# Motor.net
KiCad netlist of a schematic drawn in Altium Designer
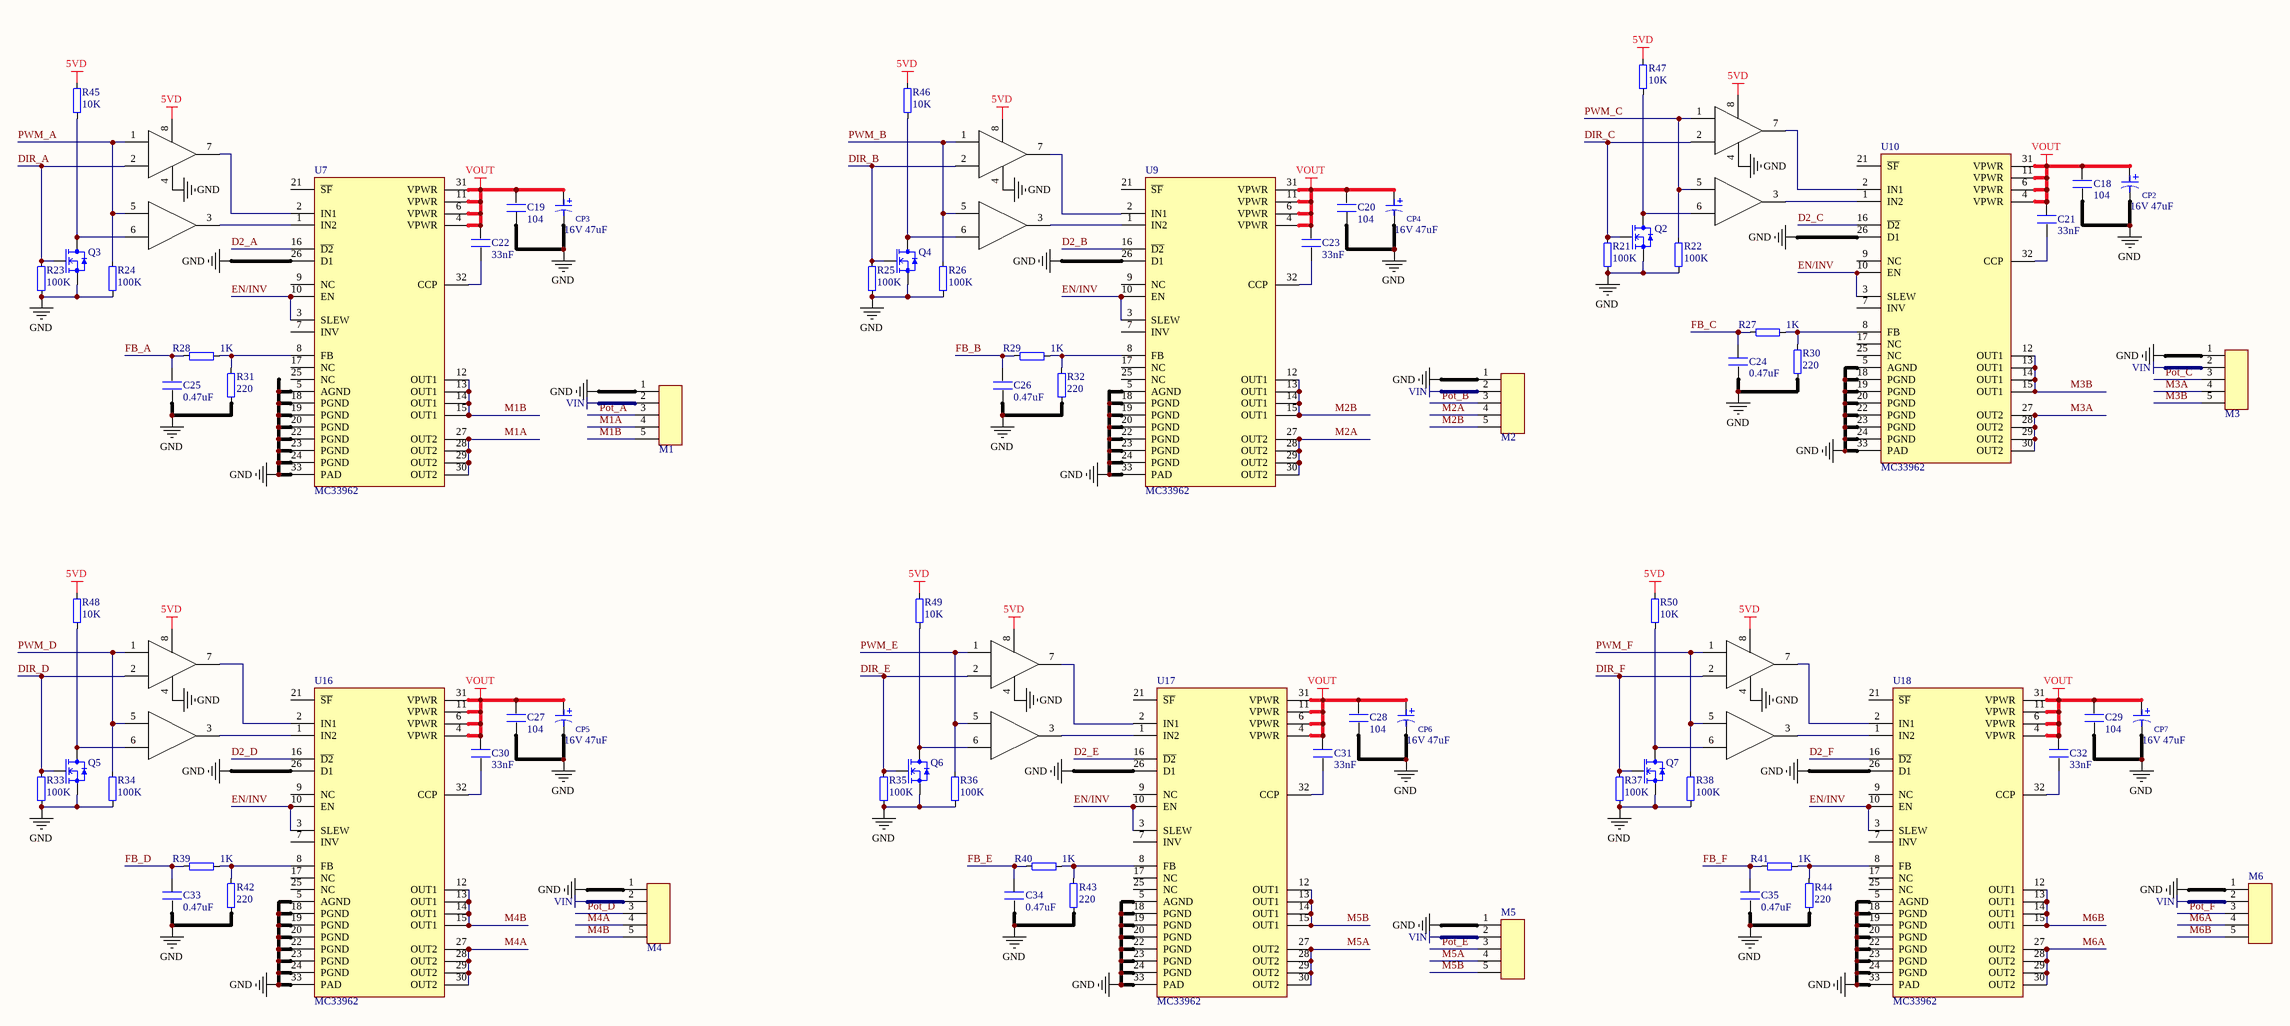
[diagram p0: Motor.SchDoc]

(export (version "E")
  (design (tool "Eeschema 10.0.6"))
  (components
    (comp (ref "C18") (value "104") (footprint "SM0603C") (libsource (lib "BAO") (part "C")))
    (comp (ref "C19") (value "104") (footprint "SM0603C") (libsource (lib "BAO") (part "C")))
    (comp (ref "C20") (value "104") (footprint "SM0603C") (libsource (lib "BAO") (part "C")))
    (comp (ref "C21") (value "33nF") (footprint "SM0603C") (libsource (lib "BAO") (part "C")))
    (comp (ref "C22") (value "33nF") (footprint "SM0603C") (libsource (lib "BAO") (part "C")))
    (comp (ref "C23") (value "33nF") (footprint "SM0603C") (libsource (lib "BAO") (part "C")))
    (comp (ref "C24") (value "0.47uF") (footprint "SM0603C") (libsource (lib "BAO") (part "C")))
    (comp (ref "C25") (value "0.47uF") (footprint "SM0603C") (libsource (lib "BAO") (part "C")))
    (comp (ref "C26") (value "0.47uF") (footprint "SM0603C") (libsource (lib "BAO") (part "C")))
    (comp (ref "C27") (value "104") (footprint "SM0603C") (libsource (lib "BAO") (part "C")))
    (comp (ref "C28") (value "104") (footprint "SM0603C") (libsource (lib "BAO") (part "C")))
    (comp (ref "C29") (value "104") (footprint "SM0603C") (libsource (lib "BAO") (part "C")))
    (comp (ref "C30") (value "33nF") (footprint "SM0603C") (libsource (lib "BAO") (part "C")))
    (comp (ref "C31") (value "33nF") (footprint "SM0603C") (libsource (lib "BAO") (part "C")))
    (comp (ref "C32") (value "33nF") (footprint "SM0603C") (libsource (lib "BAO") (part "C")))
    (comp (ref "C33") (value "0.47uF") (footprint "SM0603C") (libsource (lib "BAO") (part "C")))
    (comp (ref "C34") (value "0.47uF") (footprint "SM0603C") (libsource (lib "BAO") (part "C")))
    (comp (ref "C35") (value "0.47uF") (footprint "SM0603C") (libsource (lib "BAO") (part "C")))
    (comp (ref "CP2")
      (value "16V 47uF")
      (footprint "SMD5-Al")
      (description "Cap, 22uF, 20%, 16V")
      (libsource (lib "DigiMagusLib_CIS") (part "Cap Pol"))
    )
    (comp (ref "CP3")
      (value "16V 47uF")
      (footprint "SMD5-Al")
      (description "Cap, 22uF, 20%, 16V")
      (libsource (lib "DigiMagusLib_CIS") (part "Cap Pol"))
    )
    (comp (ref "CP4")
      (value "16V 47uF")
      (footprint "SMD5-Al")
      (description "Cap, 22uF, 20%, 16V")
      (libsource (lib "DigiMagusLib_CIS") (part "Cap Pol"))
    )
    (comp (ref "CP5")
      (value "16V 47uF")
      (footprint "SMD5-Al")
      (description "Cap, 22uF, 20%, 16V")
      (libsource (lib "DigiMagusLib_CIS") (part "Cap Pol"))
    )
    (comp (ref "CP6")
      (value "16V 47uF")
      (footprint "SMD5-Al")
      (description "Cap, 22uF, 20%, 16V")
      (libsource (lib "DigiMagusLib_CIS") (part "Cap Pol"))
    )
    (comp (ref "CP7")
      (value "16V 47uF")
      (footprint "SMD5-Al")
      (description "Cap, 22uF, 20%, 16V")
      (libsource (lib "DigiMagusLib_CIS") (part "Cap Pol"))
    )
    (comp (ref "M1") (value "JC5") (footprint "FCI_SFW5R-1STE1LF") (libsource (lib "Schlib1") (part "JC5")))
    (comp (ref "M2") (value "JC5") (footprint "FCI_SFW5R-1STE1LF") (libsource (lib "Schlib1") (part "JC5")))
    (comp (ref "M3") (value "JC5") (footprint "FCI_SFW5R-1STE1LF") (libsource (lib "Schlib1") (part "JC5")))
    (comp (ref "M4") (value "JC5") (footprint "FCI_SFW5R-1STE1LF") (libsource (lib "Schlib1") (part "JC5")))
    (comp (ref "M5") (value "JC5") (footprint "FCI_SFW5R-1STE1LF") (libsource (lib "Schlib1") (part "JC5")))
    (comp (ref "M6") (value "JC5") (footprint "FCI_SFW5R-1STE1LF") (libsource (lib "Schlib1") (part "JC5")))
    (comp (ref "Q2")
      (value "2N7002")
      (footprint "SOT23-3")
      (description "Mos/N, 2N7002, 7.5 OHM, 0.5A, SOT23-3, Supertex")
      (fields (field (name "PART NUMBER") "2.1.4.40.0270020"))
      (libsource (lib "DigiMagusLib_CIS") (part "MofFet-N"))
    )
    (comp (ref "Q3")
      (value "2N7002")
      (footprint "SOT23-3")
      (description "Mos/N, 2N7002, 7.5 OHM, 0.5A, SOT23-3, Supertex")
      (fields (field (name "PART NUMBER") "2.1.4.40.0270020"))
      (libsource (lib "DigiMagusLib_CIS") (part "MofFet-N"))
    )
    (comp (ref "Q4")
      (value "2N7002")
      (footprint "SOT23-3")
      (description "Mos/N, 2N7002, 7.5 OHM, 0.5A, SOT23-3, Supertex")
      (fields (field (name "PART NUMBER") "2.1.4.40.0270020"))
      (libsource (lib "DigiMagusLib_CIS") (part "MofFet-N"))
    )
    (comp (ref "Q5")
      (value "2N7002")
      (footprint "SOT23-3")
      (description "Mos/N, 2N7002, 7.5 OHM, 0.5A, SOT23-3, Supertex")
      (fields (field (name "PART NUMBER") "2.1.4.40.0270020"))
      (libsource (lib "DigiMagusLib_CIS") (part "MofFet-N"))
    )
    (comp (ref "Q6")
      (value "2N7002")
      (footprint "SOT23-3")
      (description "Mos/N, 2N7002, 7.5 OHM, 0.5A, SOT23-3, Supertex")
      (fields (field (name "PART NUMBER") "2.1.4.40.0270020"))
      (libsource (lib "DigiMagusLib_CIS") (part "MofFet-N"))
    )
    (comp (ref "Q7")
      (value "2N7002")
      (footprint "SOT23-3")
      (description "Mos/N, 2N7002, 7.5 OHM, 0.5A, SOT23-3, Supertex")
      (fields (field (name "PART NUMBER") "2.1.4.40.0270020"))
      (libsource (lib "DigiMagusLib_CIS") (part "MofFet-N"))
    )
    (comp (ref "R21") (value "100K") (footprint "SM0603R") (libsource (lib "电阻") (part "RES")))
    (comp (ref "R22") (value "100K") (footprint "SM0603R") (libsource (lib "电阻") (part "RES")))
    (comp (ref "R23") (value "100K") (footprint "SM0603R") (libsource (lib "电阻") (part "RES")))
    (comp (ref "R24") (value "100K") (footprint "SM0603R") (libsource (lib "电阻") (part "RES")))
    (comp (ref "R25") (value "100K") (footprint "SM0603R") (libsource (lib "电阻") (part "RES")))
    (comp (ref "R26") (value "100K") (footprint "SM0603R") (libsource (lib "电阻") (part "RES")))
    (comp (ref "R27") (value "1K") (footprint "SM0603R") (libsource (lib "电阻") (part "RES")))
    (comp (ref "R28") (value "1K") (footprint "SM0603R") (libsource (lib "电阻") (part "RES")))
    (comp (ref "R29") (value "1K") (footprint "SM0603R") (libsource (lib "电阻") (part "RES")))
    (comp (ref "R30") (value "220") (footprint "SM0603R") (libsource (lib "电阻") (part "RES")))
    (comp (ref "R31") (value "220") (footprint "SM0603R") (libsource (lib "电阻") (part "RES")))
    (comp (ref "R32") (value "220") (footprint "SM0603R") (libsource (lib "电阻") (part "RES")))
    (comp (ref "R33") (value "100K") (footprint "SM0603R") (libsource (lib "电阻") (part "RES")))
    (comp (ref "R34") (value "100K") (footprint "SM0603R") (libsource (lib "电阻") (part "RES")))
    (comp (ref "R35") (value "100K") (footprint "SM0603R") (libsource (lib "电阻") (part "RES")))
    (comp (ref "R36") (value "100K") (footprint "SM0603R") (libsource (lib "电阻") (part "RES")))
    (comp (ref "R37") (value "100K") (footprint "SM0603R") (libsource (lib "电阻") (part "RES")))
    (comp (ref "R38") (value "100K") (footprint "SM0603R") (libsource (lib "电阻") (part "RES")))
    (comp (ref "R39") (value "1K") (footprint "SM0603R") (libsource (lib "电阻") (part "RES")))
    (comp (ref "R40") (value "1K") (footprint "SM0603R") (libsource (lib "电阻") (part "RES")))
    (comp (ref "R41") (value "1K") (footprint "SM0603R") (libsource (lib "电阻") (part "RES")))
    (comp (ref "R42") (value "220") (footprint "SM0603R") (libsource (lib "电阻") (part "RES")))
    (comp (ref "R43") (value "220") (footprint "SM0603R") (libsource (lib "电阻") (part "RES")))
    (comp (ref "R44") (value "220") (footprint "SM0603R") (libsource (lib "电阻") (part "RES")))
    (comp (ref "R45") (value "10K") (footprint "SM0603R") (libsource (lib "电阻") (part "RES")))
    (comp (ref "R46") (value "10K") (footprint "SM0603R") (libsource (lib "电阻") (part "RES")))
    (comp (ref "R47") (value "10K") (footprint "SM0603R") (libsource (lib "电阻") (part "RES")))
    (comp (ref "R48") (value "10K") (footprint "SM0603R") (libsource (lib "电阻") (part "RES")))
    (comp (ref "R49") (value "10K") (footprint "SM0603R") (libsource (lib "电阻") (part "RES")))
    (comp (ref "R50") (value "10K") (footprint "SM0603R") (libsource (lib "电阻") (part "RES")))
    (comp (ref "U4")
      (value "74XXX")
      (footprint "LC-VSSOP-8_2x2.3x05P")
      (libsource (lib "Project") (part "74XXX"))
    )
    (comp (ref "U5")
      (value "74XXX")
      (footprint "LC-VSSOP-8_2x2.3x05P")
      (libsource (lib "Project") (part "74XXX"))
    )
    (comp (ref "U6")
      (value "74XXX")
      (footprint "LC-VSSOP-8_2x2.3x05P")
      (libsource (lib "Project") (part "74XXX"))
    )
    (comp (ref "U7")
      (value "MC33962")
      (footprint "PQFN32_0P8_8X8_SLUG")
      (libsource (lib "Schlib1") (part "MC33962"))
    )
    (comp (ref "U8")
      (value "74XXX")
      (footprint "LC-VSSOP-8_2x2.3x05P")
      (libsource (lib "Project") (part "74XXX"))
    )
    (comp (ref "U9")
      (value "MC33962")
      (footprint "PQFN32_0P8_8X8_SLUG")
      (libsource (lib "Schlib1") (part "MC33962"))
    )
    (comp (ref "U10")
      (value "MC33962")
      (footprint "PQFN32_0P8_8X8_SLUG")
      (libsource (lib "Schlib1") (part "MC33962"))
    )
    (comp (ref "U11")
      (value "74XXX")
      (footprint "LC-VSSOP-8_2x2.3x05P")
      (libsource (lib "Project") (part "74XXX"))
    )
    (comp (ref "U12")
      (value "74XXX")
      (footprint "LC-VSSOP-8_2x2.3x05P")
      (libsource (lib "Project") (part "74XXX"))
    )
    (comp (ref "U16")
      (value "MC33962")
      (footprint "PQFN32_0P8_8X8_SLUG")
      (libsource (lib "Schlib1") (part "MC33962"))
    )
    (comp (ref "U17")
      (value "MC33962")
      (footprint "PQFN32_0P8_8X8_SLUG")
      (libsource (lib "Schlib1") (part "MC33962"))
    )
    (comp (ref "U18")
      (value "MC33962")
      (footprint "PQFN32_0P8_8X8_SLUG")
      (libsource (lib "Schlib1") (part "MC33962"))
    )
  )
  (nets
    (net (code "1") (name "/D2_A") (class "Default")
      (node (ref "U7") (pin "16") (pinfunction "~{D2}_16") (pintype "passive"))
    )
    (net (code "2") (name "/D2_B") (class "Default")
      (node (ref "U9") (pin "16") (pinfunction "~{D2}_16") (pintype "passive"))
    )
    (net (code "3") (name "/D2_C") (class "Default")
      (node (ref "U10") (pin "16") (pinfunction "~{D2}_16") (pintype "passive"))
    )
    (net (code "4") (name "/D2_D") (class "Default")
      (node (ref "U16") (pin "16") (pinfunction "~{D2}_16") (pintype "passive"))
    )
    (net (code "5") (name "/D2_E") (class "Default")
      (node (ref "U17") (pin "16") (pinfunction "~{D2}_16") (pintype "passive"))
    )
    (net (code "6") (name "/D2_F") (class "Default")
      (node (ref "U18") (pin "16") (pinfunction "~{D2}_16") (pintype "passive"))
    )
    (net (code "7") (name "/DIR_A") (class "Default")
      (node (ref "Q3") (pin "1") (pinfunction "G_1") (pintype "passive"))
      (node (ref "R23") (pin "2") (pinfunction "2_2") (pintype "passive"))
      (node (ref "U4") (pin "2") (pinfunction "2_2") (pintype "passive"))
    )
    (net (code "8") (name "/DIR_B") (class "Default")
      (node (ref "Q4") (pin "1") (pinfunction "G_1") (pintype "passive"))
      (node (ref "R25") (pin "2") (pinfunction "2_2") (pintype "passive"))
      (node (ref "U5") (pin "2") (pinfunction "2_2") (pintype "passive"))
    )
    (net (code "9") (name "/DIR_C") (class "Default")
      (node (ref "Q2") (pin "1") (pinfunction "G_1") (pintype "passive"))
      (node (ref "R21") (pin "2") (pinfunction "2_2") (pintype "passive"))
      (node (ref "U6") (pin "2") (pinfunction "2_2") (pintype "passive"))
    )
    (net (code "10") (name "/DIR_D") (class "Default")
      (node (ref "Q5") (pin "1") (pinfunction "G_1") (pintype "passive"))
      (node (ref "R33") (pin "2") (pinfunction "2_2") (pintype "passive"))
      (node (ref "U8") (pin "2") (pinfunction "2_2") (pintype "passive"))
    )
    (net (code "11") (name "/DIR_E") (class "Default")
      (node (ref "Q6") (pin "1") (pinfunction "G_1") (pintype "passive"))
      (node (ref "R35") (pin "2") (pinfunction "2_2") (pintype "passive"))
      (node (ref "U11") (pin "2") (pinfunction "2_2") (pintype "passive"))
    )
    (net (code "12") (name "/DIR_F") (class "Default")
      (node (ref "Q7") (pin "1") (pinfunction "G_1") (pintype "passive"))
      (node (ref "R37") (pin "2") (pinfunction "2_2") (pintype "passive"))
      (node (ref "U12") (pin "2") (pinfunction "2_2") (pintype "passive"))
    )
    (net (code "13") (name "/EN{slash}INV") (class "Default")
      (node (ref "U10") (pin "10") (pinfunction "EN_10") (pintype "passive"))
      (node (ref "U10") (pin "3") (pinfunction "SLEW_3") (pintype "passive"))
      (node (ref "U16") (pin "10") (pinfunction "EN_10") (pintype "passive"))
      (node (ref "U16") (pin "3") (pinfunction "SLEW_3") (pintype "passive"))
      (node (ref "U17") (pin "10") (pinfunction "EN_10") (pintype "passive"))
      (node (ref "U17") (pin "3") (pinfunction "SLEW_3") (pintype "passive"))
      (node (ref "U18") (pin "10") (pinfunction "EN_10") (pintype "passive"))
      (node (ref "U18") (pin "3") (pinfunction "SLEW_3") (pintype "passive"))
      (node (ref "U7") (pin "10") (pinfunction "EN_10") (pintype "passive"))
      (node (ref "U7") (pin "3") (pinfunction "SLEW_3") (pintype "passive"))
      (node (ref "U9") (pin "10") (pinfunction "EN_10") (pintype "passive"))
      (node (ref "U9") (pin "3") (pinfunction "SLEW_3") (pintype "passive"))
    )
    (net (code "14") (name "/FB_A") (class "Default")
      (node (ref "C25") (pin "1") (pintype "passive"))
      (node (ref "R28") (pin "1") (pinfunction "1_1") (pintype "passive"))
    )
    (net (code "15") (name "/FB_B") (class "Default")
      (node (ref "C26") (pin "1") (pintype "passive"))
      (node (ref "R29") (pin "1") (pinfunction "1_1") (pintype "passive"))
    )
    (net (code "16") (name "/FB_C") (class "Default")
      (node (ref "C24") (pin "1") (pintype "passive"))
      (node (ref "R27") (pin "1") (pinfunction "1_1") (pintype "passive"))
    )
    (net (code "17") (name "/FB_D") (class "Default")
      (node (ref "C33") (pin "1") (pintype "passive"))
      (node (ref "R39") (pin "1") (pinfunction "1_1") (pintype "passive"))
    )
    (net (code "18") (name "/FB_E") (class "Default")
      (node (ref "C34") (pin "1") (pintype "passive"))
      (node (ref "R40") (pin "1") (pinfunction "1_1") (pintype "passive"))
    )
    (net (code "19") (name "/FB_F") (class "Default")
      (node (ref "C35") (pin "1") (pintype "passive"))
      (node (ref "R41") (pin "1") (pinfunction "1_1") (pintype "passive"))
    )
    (net (code "20") (name "/M1A") (class "Default")
      (node (ref "M1") (pin "4") (pinfunction "4_4") (pintype "passive"))
      (node (ref "U7") (pin "27") (pinfunction "OUT2_27") (pintype "passive"))
      (node (ref "U7") (pin "28") (pinfunction "OUT2_28") (pintype "passive"))
      (node (ref "U7") (pin "29") (pinfunction "OUT2_29") (pintype "passive"))
      (node (ref "U7") (pin "30") (pinfunction "OUT2_30") (pintype "passive"))
    )
    (net (code "21") (name "/M1B") (class "Default")
      (node (ref "M1") (pin "5") (pinfunction "5_5") (pintype "passive"))
      (node (ref "U7") (pin "12") (pinfunction "OUT1_12") (pintype "passive"))
      (node (ref "U7") (pin "13") (pinfunction "OUT1_13") (pintype "passive"))
      (node (ref "U7") (pin "14") (pinfunction "OUT1_14") (pintype "passive"))
      (node (ref "U7") (pin "15") (pinfunction "OUT1_15") (pintype "passive"))
    )
    (net (code "22") (name "/M2A") (class "Default")
      (node (ref "M2") (pin "4") (pinfunction "4_4") (pintype "passive"))
      (node (ref "U9") (pin "27") (pinfunction "OUT2_27") (pintype "passive"))
      (node (ref "U9") (pin "28") (pinfunction "OUT2_28") (pintype "passive"))
      (node (ref "U9") (pin "29") (pinfunction "OUT2_29") (pintype "passive"))
      (node (ref "U9") (pin "30") (pinfunction "OUT2_30") (pintype "passive"))
    )
    (net (code "23") (name "/M2B") (class "Default")
      (node (ref "M2") (pin "5") (pinfunction "5_5") (pintype "passive"))
      (node (ref "U9") (pin "12") (pinfunction "OUT1_12") (pintype "passive"))
      (node (ref "U9") (pin "13") (pinfunction "OUT1_13") (pintype "passive"))
      (node (ref "U9") (pin "14") (pinfunction "OUT1_14") (pintype "passive"))
      (node (ref "U9") (pin "15") (pinfunction "OUT1_15") (pintype "passive"))
    )
    (net (code "24") (name "/M3A") (class "Default")
      (node (ref "M3") (pin "4") (pinfunction "4_4") (pintype "passive"))
      (node (ref "U10") (pin "27") (pinfunction "OUT2_27") (pintype "passive"))
      (node (ref "U10") (pin "28") (pinfunction "OUT2_28") (pintype "passive"))
      (node (ref "U10") (pin "29") (pinfunction "OUT2_29") (pintype "passive"))
      (node (ref "U10") (pin "30") (pinfunction "OUT2_30") (pintype "passive"))
    )
    (net (code "25") (name "/M3B") (class "Default")
      (node (ref "M3") (pin "5") (pinfunction "5_5") (pintype "passive"))
      (node (ref "U10") (pin "12") (pinfunction "OUT1_12") (pintype "passive"))
      (node (ref "U10") (pin "13") (pinfunction "OUT1_13") (pintype "passive"))
      (node (ref "U10") (pin "14") (pinfunction "OUT1_14") (pintype "passive"))
      (node (ref "U10") (pin "15") (pinfunction "OUT1_15") (pintype "passive"))
    )
    (net (code "26") (name "/M4A") (class "Default")
      (node (ref "M4") (pin "4") (pinfunction "4_4") (pintype "passive"))
      (node (ref "U16") (pin "27") (pinfunction "OUT2_27") (pintype "passive"))
      (node (ref "U16") (pin "28") (pinfunction "OUT2_28") (pintype "passive"))
      (node (ref "U16") (pin "29") (pinfunction "OUT2_29") (pintype "passive"))
      (node (ref "U16") (pin "30") (pinfunction "OUT2_30") (pintype "passive"))
    )
    (net (code "27") (name "/M4B") (class "Default")
      (node (ref "M4") (pin "5") (pinfunction "5_5") (pintype "passive"))
      (node (ref "U16") (pin "12") (pinfunction "OUT1_12") (pintype "passive"))
      (node (ref "U16") (pin "13") (pinfunction "OUT1_13") (pintype "passive"))
      (node (ref "U16") (pin "14") (pinfunction "OUT1_14") (pintype "passive"))
      (node (ref "U16") (pin "15") (pinfunction "OUT1_15") (pintype "passive"))
    )
    (net (code "28") (name "/M5A") (class "Default")
      (node (ref "M5") (pin "4") (pinfunction "4_4") (pintype "passive"))
      (node (ref "U17") (pin "27") (pinfunction "OUT2_27") (pintype "passive"))
      (node (ref "U17") (pin "28") (pinfunction "OUT2_28") (pintype "passive"))
      (node (ref "U17") (pin "29") (pinfunction "OUT2_29") (pintype "passive"))
      (node (ref "U17") (pin "30") (pinfunction "OUT2_30") (pintype "passive"))
    )
    (net (code "29") (name "/M5B") (class "Default")
      (node (ref "M5") (pin "5") (pinfunction "5_5") (pintype "passive"))
      (node (ref "U17") (pin "12") (pinfunction "OUT1_12") (pintype "passive"))
      (node (ref "U17") (pin "13") (pinfunction "OUT1_13") (pintype "passive"))
      (node (ref "U17") (pin "14") (pinfunction "OUT1_14") (pintype "passive"))
      (node (ref "U17") (pin "15") (pinfunction "OUT1_15") (pintype "passive"))
    )
    (net (code "30") (name "/M6A") (class "Default")
      (node (ref "M6") (pin "4") (pinfunction "4_4") (pintype "passive"))
      (node (ref "U18") (pin "27") (pinfunction "OUT2_27") (pintype "passive"))
      (node (ref "U18") (pin "28") (pinfunction "OUT2_28") (pintype "passive"))
      (node (ref "U18") (pin "29") (pinfunction "OUT2_29") (pintype "passive"))
      (node (ref "U18") (pin "30") (pinfunction "OUT2_30") (pintype "passive"))
    )
    (net (code "31") (name "/M6B") (class "Default")
      (node (ref "M6") (pin "5") (pinfunction "5_5") (pintype "passive"))
      (node (ref "U18") (pin "12") (pinfunction "OUT1_12") (pintype "passive"))
      (node (ref "U18") (pin "13") (pinfunction "OUT1_13") (pintype "passive"))
      (node (ref "U18") (pin "14") (pinfunction "OUT1_14") (pintype "passive"))
      (node (ref "U18") (pin "15") (pinfunction "OUT1_15") (pintype "passive"))
    )
    (net (code "32") (name "/PWM_A") (class "Default")
      (node (ref "R24") (pin "2") (pinfunction "2_2") (pintype "passive"))
      (node (ref "U4") (pin "1") (pinfunction "1_1") (pintype "passive"))
      (node (ref "U4") (pin "5") (pinfunction "5_5") (pintype "passive"))
    )
    (net (code "33") (name "/PWM_B") (class "Default")
      (node (ref "R26") (pin "2") (pinfunction "2_2") (pintype "passive"))
      (node (ref "U5") (pin "1") (pinfunction "1_1") (pintype "passive"))
      (node (ref "U5") (pin "5") (pinfunction "5_5") (pintype "passive"))
    )
    (net (code "34") (name "/PWM_C") (class "Default")
      (node (ref "R22") (pin "2") (pinfunction "2_2") (pintype "passive"))
      (node (ref "U6") (pin "1") (pinfunction "1_1") (pintype "passive"))
      (node (ref "U6") (pin "5") (pinfunction "5_5") (pintype "passive"))
    )
    (net (code "35") (name "/PWM_D") (class "Default")
      (node (ref "R34") (pin "2") (pinfunction "2_2") (pintype "passive"))
      (node (ref "U8") (pin "1") (pinfunction "1_1") (pintype "passive"))
      (node (ref "U8") (pin "5") (pinfunction "5_5") (pintype "passive"))
    )
    (net (code "36") (name "/PWM_E") (class "Default")
      (node (ref "R36") (pin "2") (pinfunction "2_2") (pintype "passive"))
      (node (ref "U11") (pin "1") (pinfunction "1_1") (pintype "passive"))
      (node (ref "U11") (pin "5") (pinfunction "5_5") (pintype "passive"))
    )
    (net (code "37") (name "/PWM_F") (class "Default")
      (node (ref "R38") (pin "2") (pinfunction "2_2") (pintype "passive"))
      (node (ref "U12") (pin "1") (pinfunction "1_1") (pintype "passive"))
      (node (ref "U12") (pin "5") (pinfunction "5_5") (pintype "passive"))
    )
    (net (code "38") (name "/Pot_A") (class "Default")
      (node (ref "M1") (pin "3") (pinfunction "3_3") (pintype "passive"))
    )
    (net (code "39") (name "/Pot_B") (class "Default")
      (node (ref "M2") (pin "3") (pinfunction "3_3") (pintype "passive"))
    )
    (net (code "40") (name "/Pot_C") (class "Default")
      (node (ref "M3") (pin "3") (pinfunction "3_3") (pintype "passive"))
    )
    (net (code "41") (name "/Pot_D") (class "Default")
      (node (ref "M4") (pin "3") (pinfunction "3_3") (pintype "passive"))
    )
    (net (code "42") (name "/Pot_E") (class "Default")
      (node (ref "M5") (pin "3") (pinfunction "3_3") (pintype "passive"))
    )
    (net (code "43") (name "/Pot_F") (class "Default")
      (node (ref "M6") (pin "3") (pinfunction "3_3") (pintype "passive"))
    )
    (net (code "44") (name "5VD") (class "Default")
      (node (ref "R45") (pin "2") (pinfunction "2_2") (pintype "passive"))
      (node (ref "R46") (pin "2") (pinfunction "2_2") (pintype "passive"))
      (node (ref "R47") (pin "2") (pinfunction "2_2") (pintype "passive"))
      (node (ref "R48") (pin "2") (pinfunction "2_2") (pintype "passive"))
      (node (ref "R49") (pin "2") (pinfunction "2_2") (pintype "passive"))
      (node (ref "R50") (pin "2") (pinfunction "2_2") (pintype "passive"))
      (node (ref "U11") (pin "8") (pinfunction "8_8") (pintype "passive"))
      (node (ref "U12") (pin "8") (pinfunction "8_8") (pintype "passive"))
      (node (ref "U4") (pin "8") (pinfunction "8_8") (pintype "passive"))
      (node (ref "U5") (pin "8") (pinfunction "8_8") (pintype "passive"))
      (node (ref "U6") (pin "8") (pinfunction "8_8") (pintype "passive"))
      (node (ref "U8") (pin "8") (pinfunction "8_8") (pintype "passive"))
    )
    (net (code "45") (name "GND") (class "Default")
      (node (ref "C18") (pin "1") (pintype "passive"))
      (node (ref "C19") (pin "1") (pintype "passive"))
      (node (ref "C20") (pin "1") (pintype "passive"))
      (node (ref "C24") (pin "2") (pintype "passive"))
      (node (ref "C25") (pin "2") (pintype "passive"))
      (node (ref "C26") (pin "2") (pintype "passive"))
      (node (ref "C27") (pin "1") (pintype "passive"))
      (node (ref "C28") (pin "1") (pintype "passive"))
      (node (ref "C29") (pin "1") (pintype "passive"))
      (node (ref "C33") (pin "2") (pintype "passive"))
      (node (ref "C34") (pin "2") (pintype "passive"))
      (node (ref "C35") (pin "2") (pintype "passive"))
      (node (ref "CP2") (pin "2") (pintype "passive"))
      (node (ref "CP3") (pin "2") (pintype "passive"))
      (node (ref "CP4") (pin "2") (pintype "passive"))
      (node (ref "CP5") (pin "2") (pintype "passive"))
      (node (ref "CP6") (pin "2") (pintype "passive"))
      (node (ref "CP7") (pin "2") (pintype "passive"))
      (node (ref "M1") (pin "1") (pinfunction "1_1") (pintype "passive"))
      (node (ref "M2") (pin "1") (pinfunction "1_1") (pintype "passive"))
      (node (ref "M3") (pin "1") (pinfunction "1_1") (pintype "passive"))
      (node (ref "M4") (pin "1") (pinfunction "1_1") (pintype "passive"))
      (node (ref "M5") (pin "1") (pinfunction "1_1") (pintype "passive"))
      (node (ref "M6") (pin "1") (pinfunction "1_1") (pintype "passive"))
      (node (ref "Q2") (pin "2") (pinfunction "S_2") (pintype "passive"))
      (node (ref "Q3") (pin "2") (pinfunction "S_2") (pintype "passive"))
      (node (ref "Q4") (pin "2") (pinfunction "S_2") (pintype "passive"))
      (node (ref "Q5") (pin "2") (pinfunction "S_2") (pintype "passive"))
      (node (ref "Q6") (pin "2") (pinfunction "S_2") (pintype "passive"))
      (node (ref "Q7") (pin "2") (pinfunction "S_2") (pintype "passive"))
      (node (ref "R21") (pin "1") (pinfunction "1_1") (pintype "passive"))
      (node (ref "R22") (pin "1") (pinfunction "1_1") (pintype "passive"))
      (node (ref "R23") (pin "1") (pinfunction "1_1") (pintype "passive"))
      (node (ref "R24") (pin "1") (pinfunction "1_1") (pintype "passive"))
      (node (ref "R25") (pin "1") (pinfunction "1_1") (pintype "passive"))
      (node (ref "R26") (pin "1") (pinfunction "1_1") (pintype "passive"))
      (node (ref "R30") (pin "1") (pinfunction "1_1") (pintype "passive"))
      (node (ref "R31") (pin "1") (pinfunction "1_1") (pintype "passive"))
      (node (ref "R32") (pin "1") (pinfunction "1_1") (pintype "passive"))
      (node (ref "R33") (pin "1") (pinfunction "1_1") (pintype "passive"))
      (node (ref "R34") (pin "1") (pinfunction "1_1") (pintype "passive"))
      (node (ref "R35") (pin "1") (pinfunction "1_1") (pintype "passive"))
      (node (ref "R36") (pin "1") (pinfunction "1_1") (pintype "passive"))
      (node (ref "R37") (pin "1") (pinfunction "1_1") (pintype "passive"))
      (node (ref "R38") (pin "1") (pinfunction "1_1") (pintype "passive"))
      (node (ref "R42") (pin "1") (pinfunction "1_1") (pintype "passive"))
      (node (ref "R43") (pin "1") (pinfunction "1_1") (pintype "passive"))
      (node (ref "R44") (pin "1") (pinfunction "1_1") (pintype "passive"))
      (node (ref "U10") (pin "18") (pinfunction "PGND_18") (pintype "passive"))
      (node (ref "U10") (pin "19") (pinfunction "PGND_19") (pintype "passive"))
      (node (ref "U10") (pin "20") (pinfunction "PGND_20") (pintype "passive"))
      (node (ref "U10") (pin "22") (pinfunction "PGND_22") (pintype "passive"))
      (node (ref "U10") (pin "23") (pinfunction "PGND_23") (pintype "passive"))
      (node (ref "U10") (pin "24") (pinfunction "PGND_24") (pintype "passive"))
      (node (ref "U10") (pin "26") (pinfunction "D1_26") (pintype "passive"))
      (node (ref "U10") (pin "33") (pinfunction "PAD_33") (pintype "passive"))
      (node (ref "U10") (pin "5") (pinfunction "AGND_5") (pintype "passive"))
      (node (ref "U11") (pin "4") (pinfunction "4_4") (pintype "passive"))
      (node (ref "U12") (pin "4") (pinfunction "4_4") (pintype "passive"))
      (node (ref "U16") (pin "18") (pinfunction "PGND_18") (pintype "passive"))
      (node (ref "U16") (pin "19") (pinfunction "PGND_19") (pintype "passive"))
      (node (ref "U16") (pin "20") (pinfunction "PGND_20") (pintype "passive"))
      (node (ref "U16") (pin "22") (pinfunction "PGND_22") (pintype "passive"))
      (node (ref "U16") (pin "23") (pinfunction "PGND_23") (pintype "passive"))
      (node (ref "U16") (pin "24") (pinfunction "PGND_24") (pintype "passive"))
      (node (ref "U16") (pin "26") (pinfunction "D1_26") (pintype "passive"))
      (node (ref "U16") (pin "33") (pinfunction "PAD_33") (pintype "passive"))
      (node (ref "U16") (pin "5") (pinfunction "AGND_5") (pintype "passive"))
      (node (ref "U17") (pin "18") (pinfunction "PGND_18") (pintype "passive"))
      (node (ref "U17") (pin "19") (pinfunction "PGND_19") (pintype "passive"))
      (node (ref "U17") (pin "20") (pinfunction "PGND_20") (pintype "passive"))
      (node (ref "U17") (pin "22") (pinfunction "PGND_22") (pintype "passive"))
      (node (ref "U17") (pin "23") (pinfunction "PGND_23") (pintype "passive"))
      (node (ref "U17") (pin "24") (pinfunction "PGND_24") (pintype "passive"))
      (node (ref "U17") (pin "26") (pinfunction "D1_26") (pintype "passive"))
      (node (ref "U17") (pin "33") (pinfunction "PAD_33") (pintype "passive"))
      (node (ref "U17") (pin "5") (pinfunction "AGND_5") (pintype "passive"))
      (node (ref "U18") (pin "18") (pinfunction "PGND_18") (pintype "passive"))
      (node (ref "U18") (pin "19") (pinfunction "PGND_19") (pintype "passive"))
      (node (ref "U18") (pin "20") (pinfunction "PGND_20") (pintype "passive"))
      (node (ref "U18") (pin "22") (pinfunction "PGND_22") (pintype "passive"))
      (node (ref "U18") (pin "23") (pinfunction "PGND_23") (pintype "passive"))
      (node (ref "U18") (pin "24") (pinfunction "PGND_24") (pintype "passive"))
      (node (ref "U18") (pin "26") (pinfunction "D1_26") (pintype "passive"))
      (node (ref "U18") (pin "33") (pinfunction "PAD_33") (pintype "passive"))
      (node (ref "U18") (pin "5") (pinfunction "AGND_5") (pintype "passive"))
      (node (ref "U4") (pin "4") (pinfunction "4_4") (pintype "passive"))
      (node (ref "U5") (pin "4") (pinfunction "4_4") (pintype "passive"))
      (node (ref "U6") (pin "4") (pinfunction "4_4") (pintype "passive"))
      (node (ref "U7") (pin "18") (pinfunction "PGND_18") (pintype "passive"))
      (node (ref "U7") (pin "19") (pinfunction "PGND_19") (pintype "passive"))
      (node (ref "U7") (pin "20") (pinfunction "PGND_20") (pintype "passive"))
      (node (ref "U7") (pin "22") (pinfunction "PGND_22") (pintype "passive"))
      (node (ref "U7") (pin "23") (pinfunction "PGND_23") (pintype "passive"))
      (node (ref "U7") (pin "24") (pinfunction "PGND_24") (pintype "passive"))
      (node (ref "U7") (pin "26") (pinfunction "D1_26") (pintype "passive"))
      (node (ref "U7") (pin "33") (pinfunction "PAD_33") (pintype "passive"))
      (node (ref "U7") (pin "5") (pinfunction "AGND_5") (pintype "passive"))
      (node (ref "U8") (pin "4") (pinfunction "4_4") (pintype "passive"))
      (node (ref "U9") (pin "18") (pinfunction "PGND_18") (pintype "passive"))
      (node (ref "U9") (pin "19") (pinfunction "PGND_19") (pintype "passive"))
      (node (ref "U9") (pin "20") (pinfunction "PGND_20") (pintype "passive"))
      (node (ref "U9") (pin "22") (pinfunction "PGND_22") (pintype "passive"))
      (node (ref "U9") (pin "23") (pinfunction "PGND_23") (pintype "passive"))
      (node (ref "U9") (pin "24") (pinfunction "PGND_24") (pintype "passive"))
      (node (ref "U9") (pin "26") (pinfunction "D1_26") (pintype "passive"))
      (node (ref "U9") (pin "33") (pinfunction "PAD_33") (pintype "passive"))
      (node (ref "U9") (pin "5") (pinfunction "AGND_5") (pintype "passive"))
    )
    (net (code "46") (name "Net-(Q2-D)") (class "Default")
      (node (ref "Q2") (pin "3") (pinfunction "D_3") (pintype "passive"))
      (node (ref "R47") (pin "1") (pinfunction "1_1") (pintype "passive"))
      (node (ref "U6") (pin "6") (pinfunction "6_6") (pintype "passive"))
    )
    (net (code "47") (name "Net-(Q3-D)") (class "Default")
      (node (ref "Q3") (pin "3") (pinfunction "D_3") (pintype "passive"))
      (node (ref "R45") (pin "1") (pinfunction "1_1") (pintype "passive"))
      (node (ref "U4") (pin "6") (pinfunction "6_6") (pintype "passive"))
    )
    (net (code "48") (name "Net-(Q4-D)") (class "Default")
      (node (ref "Q4") (pin "3") (pinfunction "D_3") (pintype "passive"))
      (node (ref "R46") (pin "1") (pinfunction "1_1") (pintype "passive"))
      (node (ref "U5") (pin "6") (pinfunction "6_6") (pintype "passive"))
    )
    (net (code "49") (name "Net-(Q5-D)") (class "Default")
      (node (ref "Q5") (pin "3") (pinfunction "D_3") (pintype "passive"))
      (node (ref "R48") (pin "1") (pinfunction "1_1") (pintype "passive"))
      (node (ref "U8") (pin "6") (pinfunction "6_6") (pintype "passive"))
    )
    (net (code "50") (name "Net-(Q6-D)") (class "Default")
      (node (ref "Q6") (pin "3") (pinfunction "D_3") (pintype "passive"))
      (node (ref "R49") (pin "1") (pinfunction "1_1") (pintype "passive"))
      (node (ref "U11") (pin "6") (pinfunction "6_6") (pintype "passive"))
    )
    (net (code "51") (name "Net-(Q7-D)") (class "Default")
      (node (ref "Q7") (pin "3") (pinfunction "D_3") (pintype "passive"))
      (node (ref "R50") (pin "1") (pinfunction "1_1") (pintype "passive"))
      (node (ref "U12") (pin "6") (pinfunction "6_6") (pintype "passive"))
    )
    (net (code "52") (name "Net-(U7-CCP)") (class "Default")
      (node (ref "C22") (pin "2") (pintype "passive"))
      (node (ref "U7") (pin "32") (pinfunction "CCP_32") (pintype "passive"))
    )
    (net (code "53") (name "Net-(U7-FB)") (class "Default")
      (node (ref "R28") (pin "2") (pinfunction "2_2") (pintype "passive"))
      (node (ref "R31") (pin "2") (pinfunction "2_2") (pintype "passive"))
      (node (ref "U7") (pin "8") (pinfunction "FB_8") (pintype "passive"))
    )
    (net (code "54") (name "Net-(U7-IN1)") (class "Default")
      (node (ref "U4") (pin "7") (pinfunction "7_7") (pintype "passive"))
      (node (ref "U7") (pin "2") (pinfunction "IN1_2") (pintype "passive"))
    )
    (net (code "55") (name "Net-(U7-IN2)") (class "Default")
      (node (ref "U4") (pin "3") (pinfunction "3_3") (pintype "passive"))
      (node (ref "U7") (pin "1") (pinfunction "IN2_1") (pintype "passive"))
    )
    (net (code "56") (name "Net-(U9-CCP)") (class "Default")
      (node (ref "C23") (pin "2") (pintype "passive"))
      (node (ref "U9") (pin "32") (pinfunction "CCP_32") (pintype "passive"))
    )
    (net (code "57") (name "Net-(U9-FB)") (class "Default")
      (node (ref "R29") (pin "2") (pinfunction "2_2") (pintype "passive"))
      (node (ref "R32") (pin "2") (pinfunction "2_2") (pintype "passive"))
      (node (ref "U9") (pin "8") (pinfunction "FB_8") (pintype "passive"))
    )
    (net (code "58") (name "Net-(U9-IN1)") (class "Default")
      (node (ref "U5") (pin "7") (pinfunction "7_7") (pintype "passive"))
      (node (ref "U9") (pin "2") (pinfunction "IN1_2") (pintype "passive"))
    )
    (net (code "59") (name "Net-(U9-IN2)") (class "Default")
      (node (ref "U5") (pin "3") (pinfunction "3_3") (pintype "passive"))
      (node (ref "U9") (pin "1") (pinfunction "IN2_1") (pintype "passive"))
    )
    (net (code "60") (name "Net-(U10-CCP)") (class "Default")
      (node (ref "C21") (pin "2") (pintype "passive"))
      (node (ref "U10") (pin "32") (pinfunction "CCP_32") (pintype "passive"))
    )
    (net (code "61") (name "Net-(U10-FB)") (class "Default")
      (node (ref "R27") (pin "2") (pinfunction "2_2") (pintype "passive"))
      (node (ref "R30") (pin "2") (pinfunction "2_2") (pintype "passive"))
      (node (ref "U10") (pin "8") (pinfunction "FB_8") (pintype "passive"))
    )
    (net (code "62") (name "Net-(U10-IN1)") (class "Default")
      (node (ref "U10") (pin "2") (pinfunction "IN1_2") (pintype "passive"))
      (node (ref "U6") (pin "7") (pinfunction "7_7") (pintype "passive"))
    )
    (net (code "63") (name "Net-(U10-IN2)") (class "Default")
      (node (ref "U10") (pin "1") (pinfunction "IN2_1") (pintype "passive"))
      (node (ref "U6") (pin "3") (pinfunction "3_3") (pintype "passive"))
    )
    (net (code "64") (name "Net-(U16-CCP)") (class "Default")
      (node (ref "C30") (pin "2") (pintype "passive"))
      (node (ref "U16") (pin "32") (pinfunction "CCP_32") (pintype "passive"))
    )
    (net (code "65") (name "Net-(U16-FB)") (class "Default")
      (node (ref "R39") (pin "2") (pinfunction "2_2") (pintype "passive"))
      (node (ref "R42") (pin "2") (pinfunction "2_2") (pintype "passive"))
      (node (ref "U16") (pin "8") (pinfunction "FB_8") (pintype "passive"))
    )
    (net (code "66") (name "Net-(U16-IN1)") (class "Default")
      (node (ref "U16") (pin "2") (pinfunction "IN1_2") (pintype "passive"))
      (node (ref "U8") (pin "7") (pinfunction "7_7") (pintype "passive"))
    )
    (net (code "67") (name "Net-(U16-IN2)") (class "Default")
      (node (ref "U16") (pin "1") (pinfunction "IN2_1") (pintype "passive"))
      (node (ref "U8") (pin "3") (pinfunction "3_3") (pintype "passive"))
    )
    (net (code "68") (name "Net-(U17-CCP)") (class "Default")
      (node (ref "C31") (pin "2") (pintype "passive"))
      (node (ref "U17") (pin "32") (pinfunction "CCP_32") (pintype "passive"))
    )
    (net (code "69") (name "Net-(U17-FB)") (class "Default")
      (node (ref "R40") (pin "2") (pinfunction "2_2") (pintype "passive"))
      (node (ref "R43") (pin "2") (pinfunction "2_2") (pintype "passive"))
      (node (ref "U17") (pin "8") (pinfunction "FB_8") (pintype "passive"))
    )
    (net (code "70") (name "Net-(U17-IN1)") (class "Default")
      (node (ref "U11") (pin "7") (pinfunction "7_7") (pintype "passive"))
      (node (ref "U17") (pin "2") (pinfunction "IN1_2") (pintype "passive"))
    )
    (net (code "71") (name "Net-(U17-IN2)") (class "Default")
      (node (ref "U11") (pin "3") (pinfunction "3_3") (pintype "passive"))
      (node (ref "U17") (pin "1") (pinfunction "IN2_1") (pintype "passive"))
    )
    (net (code "72") (name "Net-(U18-CCP)") (class "Default")
      (node (ref "C32") (pin "2") (pintype "passive"))
      (node (ref "U18") (pin "32") (pinfunction "CCP_32") (pintype "passive"))
    )
    (net (code "73") (name "Net-(U18-FB)") (class "Default")
      (node (ref "R41") (pin "2") (pinfunction "2_2") (pintype "passive"))
      (node (ref "R44") (pin "2") (pinfunction "2_2") (pintype "passive"))
      (node (ref "U18") (pin "8") (pinfunction "FB_8") (pintype "passive"))
    )
    (net (code "74") (name "Net-(U18-IN1)") (class "Default")
      (node (ref "U12") (pin "7") (pinfunction "7_7") (pintype "passive"))
      (node (ref "U18") (pin "2") (pinfunction "IN1_2") (pintype "passive"))
    )
    (net (code "75") (name "Net-(U18-IN2)") (class "Default")
      (node (ref "U12") (pin "3") (pinfunction "3_3") (pintype "passive"))
      (node (ref "U18") (pin "1") (pinfunction "IN2_1") (pintype "passive"))
    )
    (net (code "76") (name "VIN") (class "Default")
      (node (ref "M1") (pin "2") (pinfunction "2_2") (pintype "passive"))
      (node (ref "M2") (pin "2") (pinfunction "2_2") (pintype "passive"))
      (node (ref "M3") (pin "2") (pinfunction "2_2") (pintype "passive"))
      (node (ref "M4") (pin "2") (pinfunction "2_2") (pintype "passive"))
      (node (ref "M5") (pin "2") (pinfunction "2_2") (pintype "passive"))
      (node (ref "M6") (pin "2") (pinfunction "2_2") (pintype "passive"))
    )
    (net (code "77") (name "VOUT") (class "Default")
      (node (ref "C18") (pin "2") (pintype "passive"))
      (node (ref "C19") (pin "2") (pintype "passive"))
      (node (ref "C20") (pin "2") (pintype "passive"))
      (node (ref "C21") (pin "1") (pintype "passive"))
      (node (ref "C22") (pin "1") (pintype "passive"))
      (node (ref "C23") (pin "1") (pintype "passive"))
      (node (ref "C27") (pin "2") (pintype "passive"))
      (node (ref "C28") (pin "2") (pintype "passive"))
      (node (ref "C29") (pin "2") (pintype "passive"))
      (node (ref "C30") (pin "1") (pintype "passive"))
      (node (ref "C31") (pin "1") (pintype "passive"))
      (node (ref "C32") (pin "1") (pintype "passive"))
      (node (ref "CP2") (pin "1") (pintype "passive"))
      (node (ref "CP3") (pin "1") (pintype "passive"))
      (node (ref "CP4") (pin "1") (pintype "passive"))
      (node (ref "CP5") (pin "1") (pintype "passive"))
      (node (ref "CP6") (pin "1") (pintype "passive"))
      (node (ref "CP7") (pin "1") (pintype "passive"))
      (node (ref "U10") (pin "11") (pinfunction "VPWR_11") (pintype "passive"))
      (node (ref "U10") (pin "31") (pinfunction "VPWR_31") (pintype "passive"))
      (node (ref "U10") (pin "4") (pinfunction "VPWR_4") (pintype "passive"))
      (node (ref "U10") (pin "6") (pinfunction "VPWR_6") (pintype "passive"))
      (node (ref "U16") (pin "11") (pinfunction "VPWR_11") (pintype "passive"))
      (node (ref "U16") (pin "31") (pinfunction "VPWR_31") (pintype "passive"))
      (node (ref "U16") (pin "4") (pinfunction "VPWR_4") (pintype "passive"))
      (node (ref "U16") (pin "6") (pinfunction "VPWR_6") (pintype "passive"))
      (node (ref "U17") (pin "11") (pinfunction "VPWR_11") (pintype "passive"))
      (node (ref "U17") (pin "31") (pinfunction "VPWR_31") (pintype "passive"))
      (node (ref "U17") (pin "4") (pinfunction "VPWR_4") (pintype "passive"))
      (node (ref "U17") (pin "6") (pinfunction "VPWR_6") (pintype "passive"))
      (node (ref "U18") (pin "11") (pinfunction "VPWR_11") (pintype "passive"))
      (node (ref "U18") (pin "31") (pinfunction "VPWR_31") (pintype "passive"))
      (node (ref "U18") (pin "4") (pinfunction "VPWR_4") (pintype "passive"))
      (node (ref "U18") (pin "6") (pinfunction "VPWR_6") (pintype "passive"))
      (node (ref "U7") (pin "11") (pinfunction "VPWR_11") (pintype "passive"))
      (node (ref "U7") (pin "31") (pinfunction "VPWR_31") (pintype "passive"))
      (node (ref "U7") (pin "4") (pinfunction "VPWR_4") (pintype "passive"))
      (node (ref "U7") (pin "6") (pinfunction "VPWR_6") (pintype "passive"))
      (node (ref "U9") (pin "11") (pinfunction "VPWR_11") (pintype "passive"))
      (node (ref "U9") (pin "31") (pinfunction "VPWR_31") (pintype "passive"))
      (node (ref "U9") (pin "4") (pinfunction "VPWR_4") (pintype "passive"))
      (node (ref "U9") (pin "6") (pinfunction "VPWR_6") (pintype "passive"))
    )
    (net (code "78") (name "unconnected-(U7-INV-Pad7)") (class "Default")
      (node (ref "U7") (pin "7") (pinfunction "INV_7") (pintype "passive"))
    )
    (net (code "79") (name "unconnected-(U7-NC-Pad9)") (class "Default")
      (node (ref "U7") (pin "9") (pinfunction "NC_9") (pintype "passive"))
    )
    (net (code "80") (name "unconnected-(U7-NC-Pad17)") (class "Default")
      (node (ref "U7") (pin "17") (pinfunction "NC_17") (pintype "passive"))
    )
    (net (code "81") (name "unconnected-(U7-NC-Pad25)") (class "Default")
      (node (ref "U7") (pin "25") (pinfunction "NC_25") (pintype "passive"))
    )
    (net (code "82") (name "unconnected-(U7-~{SF}-Pad21)") (class "Default")
      (node (ref "U7") (pin "21") (pinfunction "~{SF}_21") (pintype "passive"))
    )
    (net (code "83") (name "unconnected-(U9-INV-Pad7)") (class "Default")
      (node (ref "U9") (pin "7") (pinfunction "INV_7") (pintype "passive"))
    )
    (net (code "84") (name "unconnected-(U9-NC-Pad9)") (class "Default")
      (node (ref "U9") (pin "9") (pinfunction "NC_9") (pintype "passive"))
    )
    (net (code "85") (name "unconnected-(U9-NC-Pad17)") (class "Default")
      (node (ref "U9") (pin "17") (pinfunction "NC_17") (pintype "passive"))
    )
    (net (code "86") (name "unconnected-(U9-NC-Pad25)") (class "Default")
      (node (ref "U9") (pin "25") (pinfunction "NC_25") (pintype "passive"))
    )
    (net (code "87") (name "unconnected-(U9-~{SF}-Pad21)") (class "Default")
      (node (ref "U9") (pin "21") (pinfunction "~{SF}_21") (pintype "passive"))
    )
    (net (code "88") (name "unconnected-(U10-INV-Pad7)") (class "Default")
      (node (ref "U10") (pin "7") (pinfunction "INV_7") (pintype "passive"))
    )
    (net (code "89") (name "unconnected-(U10-NC-Pad9)") (class "Default")
      (node (ref "U10") (pin "9") (pinfunction "NC_9") (pintype "passive"))
    )
    (net (code "90") (name "unconnected-(U10-NC-Pad17)") (class "Default")
      (node (ref "U10") (pin "17") (pinfunction "NC_17") (pintype "passive"))
    )
    (net (code "91") (name "unconnected-(U10-NC-Pad25)") (class "Default")
      (node (ref "U10") (pin "25") (pinfunction "NC_25") (pintype "passive"))
    )
    (net (code "92") (name "unconnected-(U10-~{SF}-Pad21)") (class "Default")
      (node (ref "U10") (pin "21") (pinfunction "~{SF}_21") (pintype "passive"))
    )
    (net (code "93") (name "unconnected-(U16-INV-Pad7)") (class "Default")
      (node (ref "U16") (pin "7") (pinfunction "INV_7") (pintype "passive"))
    )
    (net (code "94") (name "unconnected-(U16-NC-Pad9)") (class "Default")
      (node (ref "U16") (pin "9") (pinfunction "NC_9") (pintype "passive"))
    )
    (net (code "95") (name "unconnected-(U16-NC-Pad17)") (class "Default")
      (node (ref "U16") (pin "17") (pinfunction "NC_17") (pintype "passive"))
    )
    (net (code "96") (name "unconnected-(U16-NC-Pad25)") (class "Default")
      (node (ref "U16") (pin "25") (pinfunction "NC_25") (pintype "passive"))
    )
    (net (code "97") (name "unconnected-(U16-~{SF}-Pad21)") (class "Default")
      (node (ref "U16") (pin "21") (pinfunction "~{SF}_21") (pintype "passive"))
    )
    (net (code "98") (name "unconnected-(U17-INV-Pad7)") (class "Default")
      (node (ref "U17") (pin "7") (pinfunction "INV_7") (pintype "passive"))
    )
    (net (code "99") (name "unconnected-(U17-NC-Pad9)") (class "Default")
      (node (ref "U17") (pin "9") (pinfunction "NC_9") (pintype "passive"))
    )
    (net (code "100") (name "unconnected-(U17-NC-Pad17)") (class "Default")
      (node (ref "U17") (pin "17") (pinfunction "NC_17") (pintype "passive"))
    )
    (net (code "101") (name "unconnected-(U17-NC-Pad25)") (class "Default")
      (node (ref "U17") (pin "25") (pinfunction "NC_25") (pintype "passive"))
    )
    (net (code "102") (name "unconnected-(U17-~{SF}-Pad21)") (class "Default")
      (node (ref "U17") (pin "21") (pinfunction "~{SF}_21") (pintype "passive"))
    )
    (net (code "103") (name "unconnected-(U18-INV-Pad7)") (class "Default")
      (node (ref "U18") (pin "7") (pinfunction "INV_7") (pintype "passive"))
    )
    (net (code "104") (name "unconnected-(U18-NC-Pad9)") (class "Default")
      (node (ref "U18") (pin "9") (pinfunction "NC_9") (pintype "passive"))
    )
    (net (code "105") (name "unconnected-(U18-NC-Pad17)") (class "Default")
      (node (ref "U18") (pin "17") (pinfunction "NC_17") (pintype "passive"))
    )
    (net (code "106") (name "unconnected-(U18-NC-Pad25)") (class "Default")
      (node (ref "U18") (pin "25") (pinfunction "NC_25") (pintype "passive"))
    )
    (net (code "107") (name "unconnected-(U18-~{SF}-Pad21)") (class "Default")
      (node (ref "U18") (pin "21") (pinfunction "~{SF}_21") (pintype "passive"))
    )
  )
)
